# p2_standby.net
KiCad netlist of a schematic drawn in Altium Designer
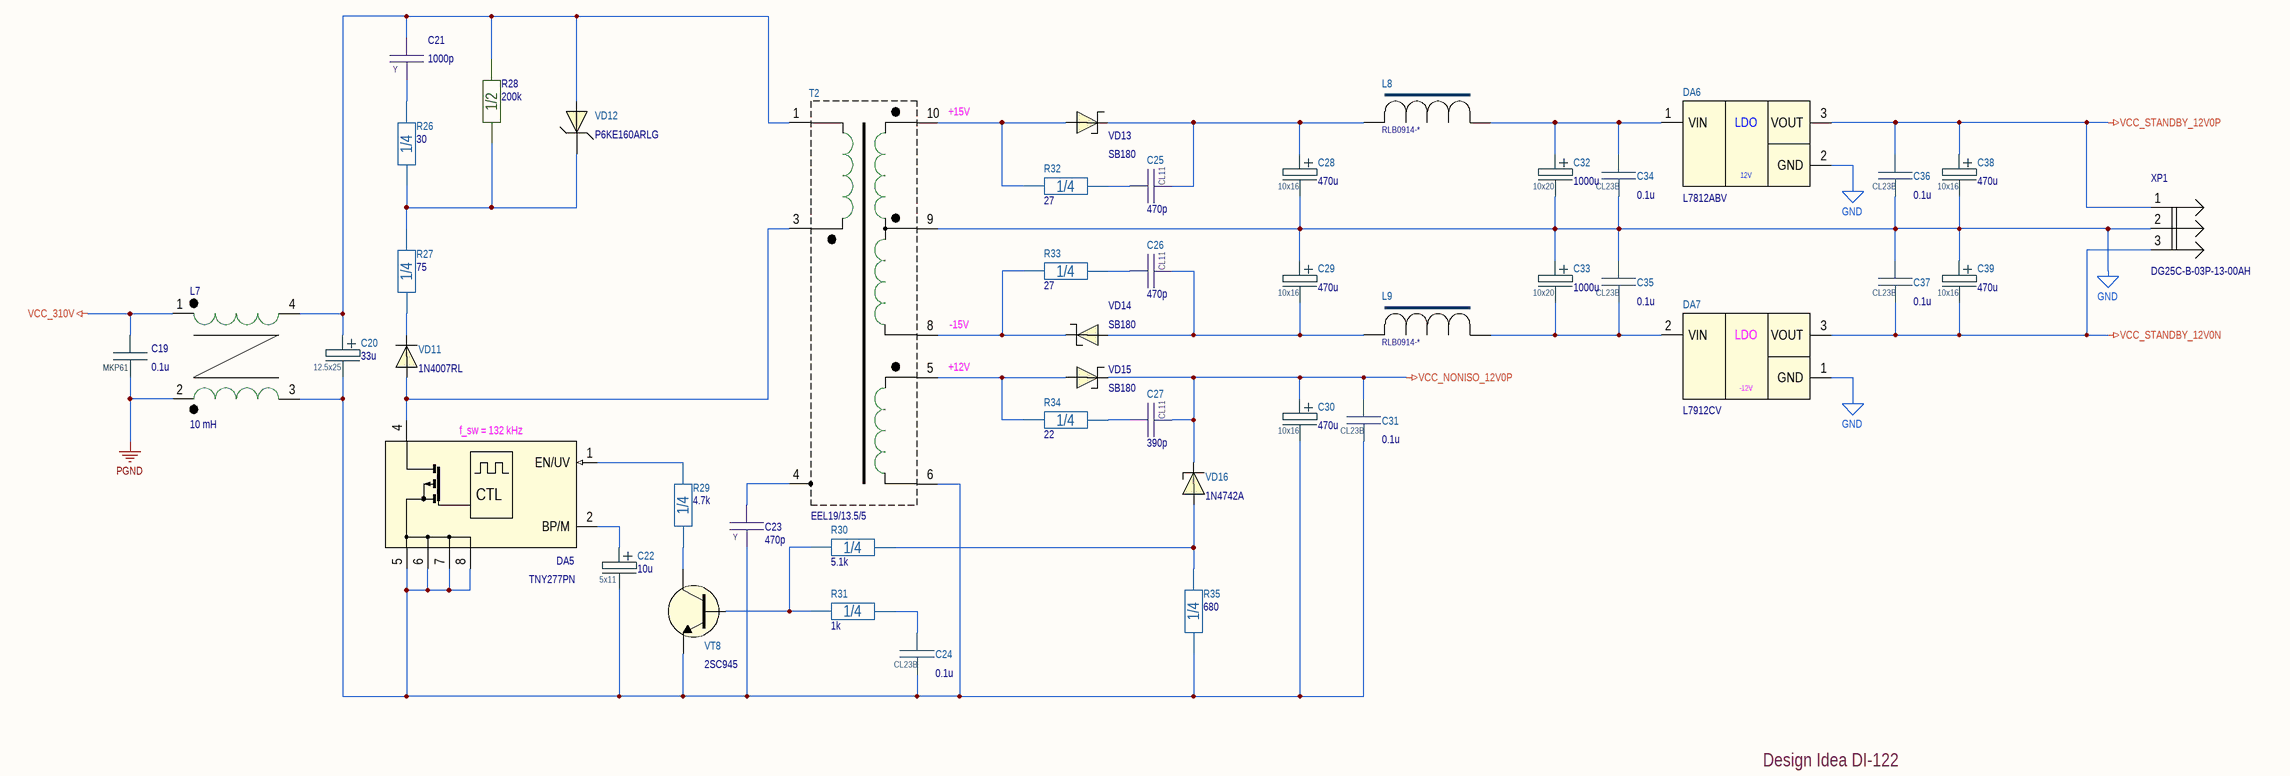
[diagram p0: p2_standby.SchDoc]

(export (version "E")
  (design (tool "Eeschema 10.0.6"))
  (components
    (comp (ref "C19")
      (value "0.1u")
      (footprint "PcbLib_RC:MKP61_13x12x6_P10")
      (description "Metallized Polypropylene Film Capacitor for high voltage application")
      (fields
        (field (name "TOLERANCE") "± 10 %")
        (field (name "VOLTAGE") "300V")
        (field (name "PACKAGE") "MKP61")
      )
      (libsource (lib "Schlib_RC") (part "MKP61"))
    )
    (comp (ref "C20")
      (value "33u")
      (footprint "PcbLib_RC:ECAP13X21X5_BRW")
      (description "Aluminium capacitor")
      (fields
        (field (name "TOLERANCE") "± 20 %")
        (field (name "VOLTAGE") "400V")
        (field (name "PACKAGE") "12.5x25")
      )
      (libsource (lib "Schlib_RC") (part "C_ECAP"))
    )
    (comp (ref "C21")
      (value "1000p")
      (footprint "PcbLib_RC:JYC_Y2_CAP_7.5")
      (description "High Voltage Ceramic Capacitor")
      (fields
        (field (name "TOLERANCE") "± 20 %")
        (field (name "VOLTAGE") "2000V")
        (field (name "PACKAGE") "Y")
      )
      (libsource (lib "Schlib_RC") (part "JB_Y2"))
    )
    (comp (ref "C22")
      (value "10u")
      (footprint "PcbLib_RC:ECAP5X11X2.0_BRW")
      (description "Aluminium capacitor")
      (fields
        (field (name "TOLERANCE") "± 20 %")
        (field (name "VOLTAGE") "63V")
        (field (name "PACKAGE") "5x11")
      )
      (libsource (lib "Schlib_RC") (part "C_ECAP"))
    )
    (comp (ref "C23")
      (value "470p")
      (footprint "PcbLib_RC:JYC_Y2_CAP_6.5")
      (description "High Voltage Ceramic Capacitor")
      (fields
        (field (name "TOLERANCE") "± 10 %")
        (field (name "VOLTAGE") "2000V")
        (field (name "PACKAGE") "Y")
      )
      (libsource (lib "Schlib_RC") (part "JB_Y2"))
    )
    (comp (ref "C24")
      (value "0.1u")
      (footprint "PcbLib_RC:CL23B_7.2x2.5")
      (description "Box-type metallized polyester film capacitor")
      (fields
        (field (name "TOLERANCE") "± * %")
        (field (name "VOLTAGE") "63V")
        (field (name "PACKAGE") "CL23B")
      )
      (libsource (lib "Schlib_RC") (part "CL23B"))
    )
    (comp (ref "C25")
      (value "470p")
      (footprint "PcbLib_RC:CL11_6x4_P4.0")
      (description "CL11 Type Polyester Film Metal Foil Capacitor-inductive")
      (fields
        (field (name "TOLERANCE") "± 5 %")
        (field (name "VOLTAGE") "100V")
        (field (name "PACKAGE") "CL11")
      )
      (libsource (lib "Schlib_RC") (part "CL11"))
    )
    (comp (ref "C26")
      (value "470p")
      (footprint "PcbLib_RC:CL11_6x4_P4.0")
      (description "CL11 Type Polyester Film Metal Foil Capacitor-inductive")
      (fields
        (field (name "TOLERANCE") "± 5 %")
        (field (name "VOLTAGE") "100V")
        (field (name "PACKAGE") "CL11")
      )
      (libsource (lib "Schlib_RC") (part "CL11"))
    )
    (comp (ref "C27")
      (value "390p")
      (footprint "PcbLib_RC:CL11_6x4_P4.0")
      (description "CL11 Type Polyester Film Metal Foil Capacitor-inductive")
      (fields
        (field (name "TOLERANCE") "± 5 %")
        (field (name "VOLTAGE") "100V")
        (field (name "PACKAGE") "CL11")
      )
      (libsource (lib "Schlib_RC") (part "CL11"))
    )
    (comp (ref "C28")
      (value "470u")
      (footprint "PcbLib_RC:ECAP10X17X5_BRW")
      (description "Aluminium capacitor")
      (fields
        (field (name "TOLERANCE") "± 20 %")
        (field (name "VOLTAGE") "25V")
        (field (name "PACKAGE") "10x16")
      )
      (libsource (lib "Schlib_RC") (part "C_ECAP"))
    )
    (comp (ref "C29")
      (value "470u")
      (footprint "PcbLib_RC:ECAP10X17X5_BRW")
      (description "Aluminium capacitor")
      (fields
        (field (name "TOLERANCE") "± 20 %")
        (field (name "VOLTAGE") "25V")
        (field (name "PACKAGE") "10x16")
      )
      (libsource (lib "Schlib_RC") (part "C_ECAP"))
    )
    (comp (ref "C30")
      (value "470u")
      (footprint "PcbLib_RC:ECAP10X17X5_BRW")
      (description "Aluminium capacitor")
      (fields
        (field (name "TOLERANCE") "± 20 %")
        (field (name "VOLTAGE") "25V")
        (field (name "PACKAGE") "10x16")
      )
      (libsource (lib "Schlib_RC") (part "C_ECAP"))
    )
    (comp (ref "C31")
      (value "0.1u")
      (footprint "PcbLib_RC:CL23B_7.2x2.5")
      (description "Box-type metallized polyester film capacitor")
      (fields
        (field (name "TOLERANCE") "± * %")
        (field (name "VOLTAGE") "63V")
        (field (name "PACKAGE") "CL23B")
      )
      (libsource (lib "Schlib_RC") (part "CL23B"))
    )
    (comp (ref "C32")
      (value "1000u")
      (footprint "PcbLib_RC:ECAP10X21X5_BRW")
      (description "Aluminium capacitor")
      (fields
        (field (name "TOLERANCE") "± 20 %")
        (field (name "VOLTAGE") "25V")
        (field (name "PACKAGE") "10x20")
      )
      (libsource (lib "Schlib_RC") (part "C_ECAP"))
    )
    (comp (ref "C33")
      (value "1000u")
      (footprint "PcbLib_RC:ECAP10X21X5_BRW")
      (description "Aluminium capacitor")
      (fields
        (field (name "TOLERANCE") "± 20 %")
        (field (name "VOLTAGE") "25V")
        (field (name "PACKAGE") "10x20")
      )
      (libsource (lib "Schlib_RC") (part "C_ECAP"))
    )
    (comp (ref "C34")
      (value "0.1u")
      (footprint "PcbLib_RC:CL23B_7.2x2.5")
      (description "Box-type metallized polyester film capacitor")
      (fields
        (field (name "TOLERANCE") "± * %")
        (field (name "VOLTAGE") "63V")
        (field (name "PACKAGE") "CL23B")
      )
      (libsource (lib "Schlib_RC") (part "CL23B"))
    )
    (comp (ref "C35")
      (value "0.1u")
      (footprint "PcbLib_RC:CL23B_7.2x2.5")
      (description "Box-type metallized polyester film capacitor")
      (fields
        (field (name "TOLERANCE") "± * %")
        (field (name "VOLTAGE") "63V")
        (field (name "PACKAGE") "CL23B")
      )
      (libsource (lib "Schlib_RC") (part "CL23B"))
    )
    (comp (ref "C36")
      (value "0.1u")
      (footprint "PcbLib_RC:CL23B_7.2x2.5")
      (description "Box-type metallized polyester film capacitor")
      (fields
        (field (name "TOLERANCE") "± * %")
        (field (name "VOLTAGE") "63V")
        (field (name "PACKAGE") "CL23B")
      )
      (libsource (lib "Schlib_RC") (part "CL23B"))
    )
    (comp (ref "C37")
      (value "0.1u")
      (footprint "PcbLib_RC:CL23B_7.2x2.5")
      (description "Box-type metallized polyester film capacitor")
      (fields
        (field (name "TOLERANCE") "± * %")
        (field (name "VOLTAGE") "63V")
        (field (name "PACKAGE") "CL23B")
      )
      (libsource (lib "Schlib_RC") (part "CL23B"))
    )
    (comp (ref "C38")
      (value "470u")
      (footprint "PcbLib_RC:ECAP10X17X5_BRW")
      (description "Aluminium capacitor")
      (fields
        (field (name "TOLERANCE") "± 20 %")
        (field (name "VOLTAGE") "25V")
        (field (name "PACKAGE") "10x16")
      )
      (libsource (lib "Schlib_RC") (part "C_ECAP"))
    )
    (comp (ref "C39")
      (value "470u")
      (footprint "PcbLib_RC:ECAP10X17X5_BRW")
      (description "Aluminium capacitor")
      (fields
        (field (name "TOLERANCE") "± 20 %")
        (field (name "VOLTAGE") "25V")
        (field (name "PACKAGE") "10x16")
      )
      (libsource (lib "Schlib_RC") (part "C_ECAP"))
    )
    (comp (ref "DA5")
      (value "TNY277PN")
      (footprint "PcbLib_ICs:DIP-8C")
      (description "Energy-Effi cient, Off-Line Switcher With Enhanced Flexibility and Extended Power Range")
      (fields (field (name "MANUFACTURER") "Power Integrations"))
      (libsource (lib "Schlib_OtherComponents") (part "TNY277PN"))
    )
    (comp (ref "DA6")
      (value "L7812ABV")
      (footprint "PcbLib_ICs:TO-220AB-3")
      (description "12V, 1,5 A voltage regulator (Fixed version)")
      (fields (field (name "MANUFACTURER") "STMicroelectronics"))
      (libsource (lib "Schlib_STMicroelectronics") (part "L7812ABV"))
    )
    (comp (ref "DA7")
      (value "L7912CV")
      (footprint "PcbLib_ICs:TO-220AB-3")
      (description "-12V, 1,5 A voltage regulator (Fixed version)")
      (fields (field (name "MANUFACTURER") "STMicroelectronics"))
      (libsource (lib "Schlib_STMicroelectronics") (part "L7912CV"))
    )
    (comp (ref "L7")
      (value "10 mH")
      (footprint "PcbLib_Others:UU9.8")
      (description "UU9.8 Ferrite Core inductor")
      (libsource (lib "Schlib_OtherComponents") (part "UU9.8"))
    )
    (comp (ref "L8")
      (value "RLB0914-*")
      (footprint "PcbLib_RC:RLB0914")
      (description "Radial Inductors")
      (fields (field (name "MANUFACTURER") "Bourns Inc."))
      (libsource (lib "Schlib_Bourns") (part "RLB0914"))
    )
    (comp (ref "L9")
      (value "RLB0914-*")
      (footprint "PcbLib_RC:RLB0914")
      (description "Radial Inductors")
      (fields (field (name "MANUFACTURER") "Bourns Inc."))
      (libsource (lib "Schlib_Bourns") (part "RLB0914"))
    )
    (comp (ref "R26")
      (value "30")
      (footprint "PcbLib_RC:CFR-25")
      (description "Resistor 1/4W")
      (fields
        (field (name "TOLERANCE") "± 1 %")
        (field (name "PART NUMBER") "MFR-25FTF52-30R")
        (field (name "PACKAGE") "1/4")
      )
      (libsource (lib "Schlib_RC") (part "CF25"))
    )
    (comp (ref "R27")
      (value "75")
      (footprint "PcbLib_RC:CFR-25")
      (description "Resistor 1/4W")
      (fields
        (field (name "TOLERANCE") "± 1 %")
        (field (name "PART NUMBER") "MFR-25FTF52-75R")
        (field (name "PACKAGE") "1/4")
      )
      (libsource (lib "Schlib_RC") (part "CF25"))
    )
    (comp (ref "R28")
      (value "200k")
      (footprint "PcbLib_RC:CFR-50")
      (description "Resistor 1/2W")
      (fields
        (field (name "TOLERANCE") "± 5 %")
        (field (name "PART NUMBER") "MFR-50JT-52-200K")
        (field (name "PACKAGE") "1/2")
      )
      (libsource (lib "Schlib_RC") (part "CF50"))
    )
    (comp (ref "R29")
      (value "4.7k")
      (footprint "PcbLib_RC:CFR-25")
      (description "Resistor 1/4W")
      (fields
        (field (name "TOLERANCE") "± 1 %")
        (field (name "PART NUMBER") "MFR-25FTF52-4K7")
        (field (name "PACKAGE") "1/4")
      )
      (libsource (lib "Schlib_RC") (part "CF25"))
    )
    (comp (ref "R30")
      (value "5.1k")
      (footprint "PcbLib_RC:CFR-25")
      (description "Resistor 1/4W")
      (fields
        (field (name "TOLERANCE") "± 1 %")
        (field (name "PART NUMBER") "MFR-25FTF52-5K1")
        (field (name "PACKAGE") "1/4")
      )
      (libsource (lib "Schlib_RC") (part "CF25"))
    )
    (comp (ref "R31")
      (value "1k")
      (footprint "PcbLib_RC:CFR-25")
      (description "Resistor 1/4W")
      (fields
        (field (name "TOLERANCE") "± 1 %")
        (field (name "PART NUMBER") "MFR-25FTF52-1K")
        (field (name "PACKAGE") "1/4")
      )
      (libsource (lib "Schlib_RC") (part "CF25"))
    )
    (comp (ref "R32")
      (value "27")
      (footprint "PcbLib_RC:CFR-25")
      (description "Resistor 1/4W")
      (fields
        (field (name "TOLERANCE") "± 1 %")
        (field (name "PART NUMBER") "MFR-25FTF52-27R")
        (field (name "PACKAGE") "1/4")
      )
      (libsource (lib "Schlib_RC") (part "CF25"))
    )
    (comp (ref "R33")
      (value "27")
      (footprint "PcbLib_RC:CFR-25")
      (description "Resistor 1/4W")
      (fields
        (field (name "TOLERANCE") "± 1 %")
        (field (name "PART NUMBER") "MFR-25FTF52-27R")
        (field (name "PACKAGE") "1/4")
      )
      (libsource (lib "Schlib_RC") (part "CF25"))
    )
    (comp (ref "R34")
      (value "22")
      (footprint "PcbLib_RC:CFR-25")
      (description "Resistor 1/4W")
      (fields
        (field (name "TOLERANCE") "± 1 %")
        (field (name "PART NUMBER") "MFR-25FTF52-22R")
        (field (name "PACKAGE") "1/4")
      )
      (libsource (lib "Schlib_RC") (part "CF25"))
    )
    (comp (ref "R35")
      (value "680")
      (footprint "PcbLib_RC:CFR-25")
      (description "Resistor 1/4W")
      (fields
        (field (name "TOLERANCE") "± 1 %")
        (field (name "PART NUMBER") "MFR-25FTF52-680R")
        (field (name "PACKAGE") "1/4")
      )
      (libsource (lib "Schlib_RC") (part "CF25"))
    )
    (comp (ref "T2")
      (value "EEL19/13.5/5")
      (footprint "PcbLib_Others:EEL19/13.5/5")
      (description "EEL19 Ferrite Core, 2 output")
      (libsource (lib "Schlib_OtherComponents") (part "EEL19_V1"))
    )
    (comp (ref "VD11")
      (value "1N4007RL")
      (footprint "PcbLib_Discrete:DO-41")
      (description "1A 1000V Standard Recovery Rectifiers Diode")
      (fields (field (name "MANUFACTURER") "ON Semiconductor"))
      (libsource (lib "Schlib_ONSemiconductor") (part "1N4007RL"))
    )
    (comp (ref "VD12")
      (value "P6KE160ARLG")
      (footprint "PcbLib_Discrete:DO-15")
      (description "600 Watt Peak Power Transient\r\nVoltage Suppressors")
      (fields (field (name "MANUFACTURER") "ON Semiconductor"))
      (libsource (lib "Schlib_ONSemiconductor") (part "P6KE160ARLG"))
    )
    (comp (ref "VD13")
      (value "SB180")
      (footprint "PcbLib_Discrete:DO-41")
      (description "1A, 80V Schottky Barrier Rectifier")
      (fields (field (name "MANUFACTURER") "ON Semiconductor"))
      (libsource (lib "Schlib_ONSemiconductor") (part "SB180"))
    )
    (comp (ref "VD14")
      (value "SB180")
      (footprint "PcbLib_Discrete:DO-41")
      (description "1A, 80V Schottky Barrier Rectifier")
      (fields (field (name "MANUFACTURER") "ON Semiconductor"))
      (libsource (lib "Schlib_ONSemiconductor") (part "SB180"))
    )
    (comp (ref "VD15")
      (value "SB180")
      (footprint "PcbLib_Discrete:DO-41")
      (description "1A, 80V Schottky Barrier Rectifier")
      (fields (field (name "MANUFACTURER") "ON Semiconductor"))
      (libsource (lib "Schlib_ONSemiconductor") (part "SB180"))
    )
    (comp (ref "VD16")
      (value "1N4742A")
      (footprint "PcbLib_Discrete:DO-41 GLASS DARK RED")
      (description "12V 1.0W ZENER DIODE")
      (fields (field (name "MANUFACTURER") "Diodes Incorporated"))
      (libsource (lib "Schlib_Diodes_Incorporated") (part "1N4742A"))
    )
    (comp (ref "VT8")
      (value "2SC945")
      (footprint "PcbLib_ICs:TO-92 (VERTICAL,LINE)")
      (description "General Purpose n-p-n Transistors")
      (fields (field (name "MANUFACTURER") "NEC"))
      (libsource (lib "Schlib_NEC") (part "2SC945"))
    )
    (comp (ref "XP1")
      (value "DG25C-B-03P-13-00AH")
      (footprint "PcbLib_Pin_Headers_part2:DG25C-B-03P-13-00AH")
      (fields (field (name "MANUFACTURER") "Degson"))
      (libsource (lib "Schlib_Pin_Headers") (part "DG25C-B-03P-13-00AH"))
    )
  )
  (nets
    (net (code "1") (name "GND") (class "Default")
      (node (ref "C28") (pin "2") (pinfunction "2_2") (pintype "passive"))
      (node (ref "C29") (pin "1") (pinfunction "1_1") (pintype "passive"))
      (node (ref "C32") (pin "2") (pinfunction "2_2") (pintype "passive"))
      (node (ref "C33") (pin "1") (pinfunction "1_1") (pintype "passive"))
      (node (ref "C34") (pin "2") (pinfunction "2_2") (pintype "passive"))
      (node (ref "C35") (pin "1") (pinfunction "1_1") (pintype "passive"))
      (node (ref "C36") (pin "2") (pinfunction "2_2") (pintype "passive"))
      (node (ref "C37") (pin "1") (pinfunction "1_1") (pintype "passive"))
      (node (ref "C38") (pin "2") (pinfunction "2_2") (pintype "passive"))
      (node (ref "C39") (pin "1") (pinfunction "1_1") (pintype "passive"))
      (node (ref "DA6") (pin "2") (pinfunction "GND_2") (pintype "passive"))
      (node (ref "DA7") (pin "1") (pinfunction "GND_1") (pintype "passive"))
      (node (ref "T2") (pin "9") (pinfunction "9_9") (pintype "passive"))
      (node (ref "XP1") (pin "2") (pinfunction "2_2") (pintype "passive"))
    )
    (net (code "2") (name "Net-(C21-Pad1)") (class "Default")
      (node (ref "C21") (pin "1") (pinfunction "1_1") (pintype "passive"))
      (node (ref "R26") (pin "1") (pinfunction "1_1") (pintype "passive"))
    )
    (net (code "3") (name "Net-(C23-Pad1)") (class "Default")
      (node (ref "C23") (pin "1") (pinfunction "1_1") (pintype "passive"))
      (node (ref "T2") (pin "4") (pinfunction "4_4") (pintype "passive"))
    )
    (net (code "4") (name "Net-(C24-Pad1)") (class "Default")
      (node (ref "C24") (pin "1") (pinfunction "1_1") (pintype "passive"))
      (node (ref "R31") (pin "2") (pinfunction "2_2") (pintype "passive"))
    )
    (net (code "5") (name "Net-(C25-Pad2)") (class "Default")
      (node (ref "C25") (pin "2") (pinfunction "2_2") (pintype "passive"))
      (node (ref "R32") (pin "1") (pinfunction "1_1") (pintype "passive"))
    )
    (net (code "6") (name "Net-(C26-Pad2)") (class "Default")
      (node (ref "C26") (pin "2") (pinfunction "2_2") (pintype "passive"))
      (node (ref "R33") (pin "1") (pinfunction "1_1") (pintype "passive"))
    )
    (net (code "7") (name "Net-(C27-Pad2)") (class "Default")
      (node (ref "C27") (pin "2") (pinfunction "2_2") (pintype "passive"))
      (node (ref "R34") (pin "1") (pinfunction "1_1") (pintype "passive"))
    )
    (net (code "8") (name "Net-(DA5-BP{slash}M)") (class "Default")
      (node (ref "C22") (pin "1") (pinfunction "1_1") (pintype "passive"))
      (node (ref "DA5") (pin "2") (pinfunction "BP/M_2") (pintype "passive"))
    )
    (net (code "9") (name "Net-(DA5-DRAIN)") (class "Default")
      (node (ref "DA5") (pin "4") (pinfunction "DRAIN_4") (pintype "passive"))
      (node (ref "T2") (pin "3") (pinfunction "3_3") (pintype "passive"))
      (node (ref "VD11") (pin "2") (pinfunction "A_2") (pintype "passive"))
    )
    (net (code "10") (name "Net-(DA5-EN{slash}UV)") (class "Default")
      (node (ref "DA5") (pin "1") (pinfunction "EN/UV_1") (pintype "input"))
      (node (ref "R29") (pin "1") (pinfunction "1_1") (pintype "passive"))
    )
    (net (code "11") (name "Net-(DA6-VIN)") (class "Default")
      (node (ref "C32") (pin "1") (pinfunction "1_1") (pintype "passive"))
      (node (ref "C34") (pin "1") (pinfunction "1_1") (pintype "passive"))
      (node (ref "DA6") (pin "1") (pinfunction "VIN_1") (pintype "power_in"))
      (node (ref "L8") (pin "2") (pinfunction "2_2") (pintype "passive"))
    )
    (net (code "12") (name "Net-(DA7-VIN)") (class "Default")
      (node (ref "C33") (pin "2") (pinfunction "2_2") (pintype "passive"))
      (node (ref "C35") (pin "2") (pinfunction "2_2") (pintype "passive"))
      (node (ref "DA7") (pin "2") (pinfunction "VIN_2") (pintype "power_in"))
      (node (ref "L9") (pin "2") (pinfunction "2_2") (pintype "passive"))
    )
    (net (code "13") (name "Net-(VD11-C)") (class "Default")
      (node (ref "R27") (pin "2") (pinfunction "2_2") (pintype "passive"))
      (node (ref "VD11") (pin "1") (pinfunction "C_1") (pintype "passive"))
    )
    (net (code "14") (name "Net-(VD12-A)") (class "Default")
      (node (ref "C20") (pin "1") (pinfunction "1_1") (pintype "passive"))
      (node (ref "C21") (pin "2") (pinfunction "2_2") (pintype "passive"))
      (node (ref "L7") (pin "4") (pinfunction "4_4") (pintype "passive"))
      (node (ref "R28") (pin "2") (pinfunction "2_2") (pintype "passive"))
      (node (ref "T2") (pin "1") (pinfunction "1_1") (pintype "passive"))
      (node (ref "VD12") (pin "2") (pinfunction "A_2") (pintype "passive"))
    )
    (net (code "15") (name "Net-(VD12-C)") (class "Default")
      (node (ref "R26") (pin "2") (pinfunction "2_2") (pintype "passive"))
      (node (ref "R27") (pin "1") (pinfunction "1_1") (pintype "passive"))
      (node (ref "R28") (pin "1") (pinfunction "1_1") (pintype "passive"))
      (node (ref "VD12") (pin "1") (pinfunction "C_1") (pintype "passive"))
    )
    (net (code "16") (name "Net-(VD13-A)") (class "Default")
      (node (ref "R32") (pin "2") (pinfunction "2_2") (pintype "passive"))
      (node (ref "T2") (pin "10") (pinfunction "10_10") (pintype "passive"))
      (node (ref "VD13") (pin "2") (pinfunction "A_2") (pintype "passive"))
    )
    (net (code "17") (name "Net-(VD13-C)") (class "Default")
      (node (ref "C25") (pin "1") (pinfunction "1_1") (pintype "passive"))
      (node (ref "C28") (pin "1") (pinfunction "1_1") (pintype "passive"))
      (node (ref "L8") (pin "1") (pinfunction "1_1") (pintype "passive"))
      (node (ref "VD13") (pin "1") (pinfunction "C_1") (pintype "passive"))
    )
    (net (code "18") (name "Net-(VD14-A)") (class "Default")
      (node (ref "C26") (pin "1") (pinfunction "1_1") (pintype "passive"))
      (node (ref "C29") (pin "2") (pinfunction "2_2") (pintype "passive"))
      (node (ref "L9") (pin "1") (pinfunction "1_1") (pintype "passive"))
      (node (ref "VD14") (pin "2") (pinfunction "A_2") (pintype "passive"))
    )
    (net (code "19") (name "Net-(VD14-C)") (class "Default")
      (node (ref "R33") (pin "2") (pinfunction "2_2") (pintype "passive"))
      (node (ref "T2") (pin "8") (pinfunction "8_8") (pintype "passive"))
      (node (ref "VD14") (pin "1") (pinfunction "C_1") (pintype "passive"))
    )
    (net (code "20") (name "Net-(VD15-A)") (class "Default")
      (node (ref "R34") (pin "2") (pinfunction "2_2") (pintype "passive"))
      (node (ref "T2") (pin "5") (pinfunction "5_5") (pintype "passive"))
      (node (ref "VD15") (pin "2") (pinfunction "A_2") (pintype "passive"))
    )
    (net (code "21") (name "Net-(VD16-ANODE)") (class "Default")
      (node (ref "R30") (pin "1") (pinfunction "1_1") (pintype "passive"))
      (node (ref "R35") (pin "1") (pinfunction "1_1") (pintype "passive"))
      (node (ref "VD16") (pin "2") (pinfunction "ANODE_2") (pintype "power_in"))
    )
    (net (code "22") (name "Net-(VT8-B)") (class "Default")
      (node (ref "R30") (pin "2") (pinfunction "2_2") (pintype "passive"))
      (node (ref "R31") (pin "1") (pinfunction "1_1") (pintype "passive"))
      (node (ref "VT8") (pin "1") (pinfunction "B_1") (pintype "passive"))
    )
    (net (code "23") (name "Net-(VT8-C)") (class "Default")
      (node (ref "R29") (pin "2") (pinfunction "2_2") (pintype "passive"))
      (node (ref "VT8") (pin "2") (pinfunction "C_2") (pintype "passive"))
    )
    (net (code "24") (name "Net-(VT8-E)") (class "Default")
      (node (ref "C20") (pin "2") (pinfunction "2_2") (pintype "passive"))
      (node (ref "C22") (pin "2") (pinfunction "2_2") (pintype "passive"))
      (node (ref "C23") (pin "2") (pinfunction "2_2") (pintype "passive"))
      (node (ref "C24") (pin "2") (pinfunction "2_2") (pintype "passive"))
      (node (ref "C30") (pin "2") (pinfunction "2_2") (pintype "passive"))
      (node (ref "C31") (pin "2") (pinfunction "2_2") (pintype "passive"))
      (node (ref "DA5") (pin "5") (pinfunction "SOURCE_5") (pintype "passive"))
      (node (ref "DA5") (pin "6") (pinfunction "SOURCE_6") (pintype "passive"))
      (node (ref "DA5") (pin "7") (pinfunction "SOURCE_7") (pintype "passive"))
      (node (ref "DA5") (pin "8") (pinfunction "SOURCE_8") (pintype "passive"))
      (node (ref "L7") (pin "3") (pinfunction "3_3") (pintype "passive"))
      (node (ref "R35") (pin "2") (pinfunction "2_2") (pintype "passive"))
      (node (ref "T2") (pin "6") (pinfunction "6_6") (pintype "passive"))
      (node (ref "VT8") (pin "3") (pinfunction "E_3") (pintype "passive"))
    )
    (net (code "25") (name "PGND") (class "Default")
      (node (ref "C19") (pin "1") (pinfunction "1_1") (pintype "passive"))
      (node (ref "L7") (pin "2") (pinfunction "2_2") (pintype "passive"))
    )
    (net (code "26") (name "VCC_310V") (class "Default")
      (node (ref "C19") (pin "2") (pinfunction "2_2") (pintype "passive"))
      (node (ref "L7") (pin "1") (pinfunction "1_1") (pintype "passive"))
    )
    (net (code "27") (name "VCC_NONISO_12V0P") (class "Default")
      (node (ref "C27") (pin "1") (pinfunction "1_1") (pintype "passive"))
      (node (ref "C30") (pin "1") (pinfunction "1_1") (pintype "passive"))
      (node (ref "C31") (pin "1") (pinfunction "1_1") (pintype "passive"))
      (node (ref "VD15") (pin "1") (pinfunction "C_1") (pintype "passive"))
      (node (ref "VD16") (pin "1") (pinfunction "CATHODE_1") (pintype "passive"))
    )
    (net (code "28") (name "VCC_STANDBY_12V0N") (class "Default")
      (node (ref "C37") (pin "2") (pinfunction "2_2") (pintype "passive"))
      (node (ref "C39") (pin "2") (pinfunction "2_2") (pintype "passive"))
      (node (ref "DA7") (pin "3") (pinfunction "VOUT_3") (pintype "power_in"))
      (node (ref "XP1") (pin "3") (pinfunction "3_3") (pintype "passive"))
    )
    (net (code "29") (name "VCC_STANDBY_12V0P") (class "Default")
      (node (ref "C36") (pin "1") (pinfunction "1_1") (pintype "passive"))
      (node (ref "C38") (pin "1") (pinfunction "1_1") (pintype "passive"))
      (node (ref "DA6") (pin "3") (pinfunction "VOUT_3") (pintype "power_in"))
      (node (ref "XP1") (pin "1") (pinfunction "1_1") (pintype "passive"))
    )
  )
)
